# Power.net
KiCad netlist of a schematic drawn in Altium Designer
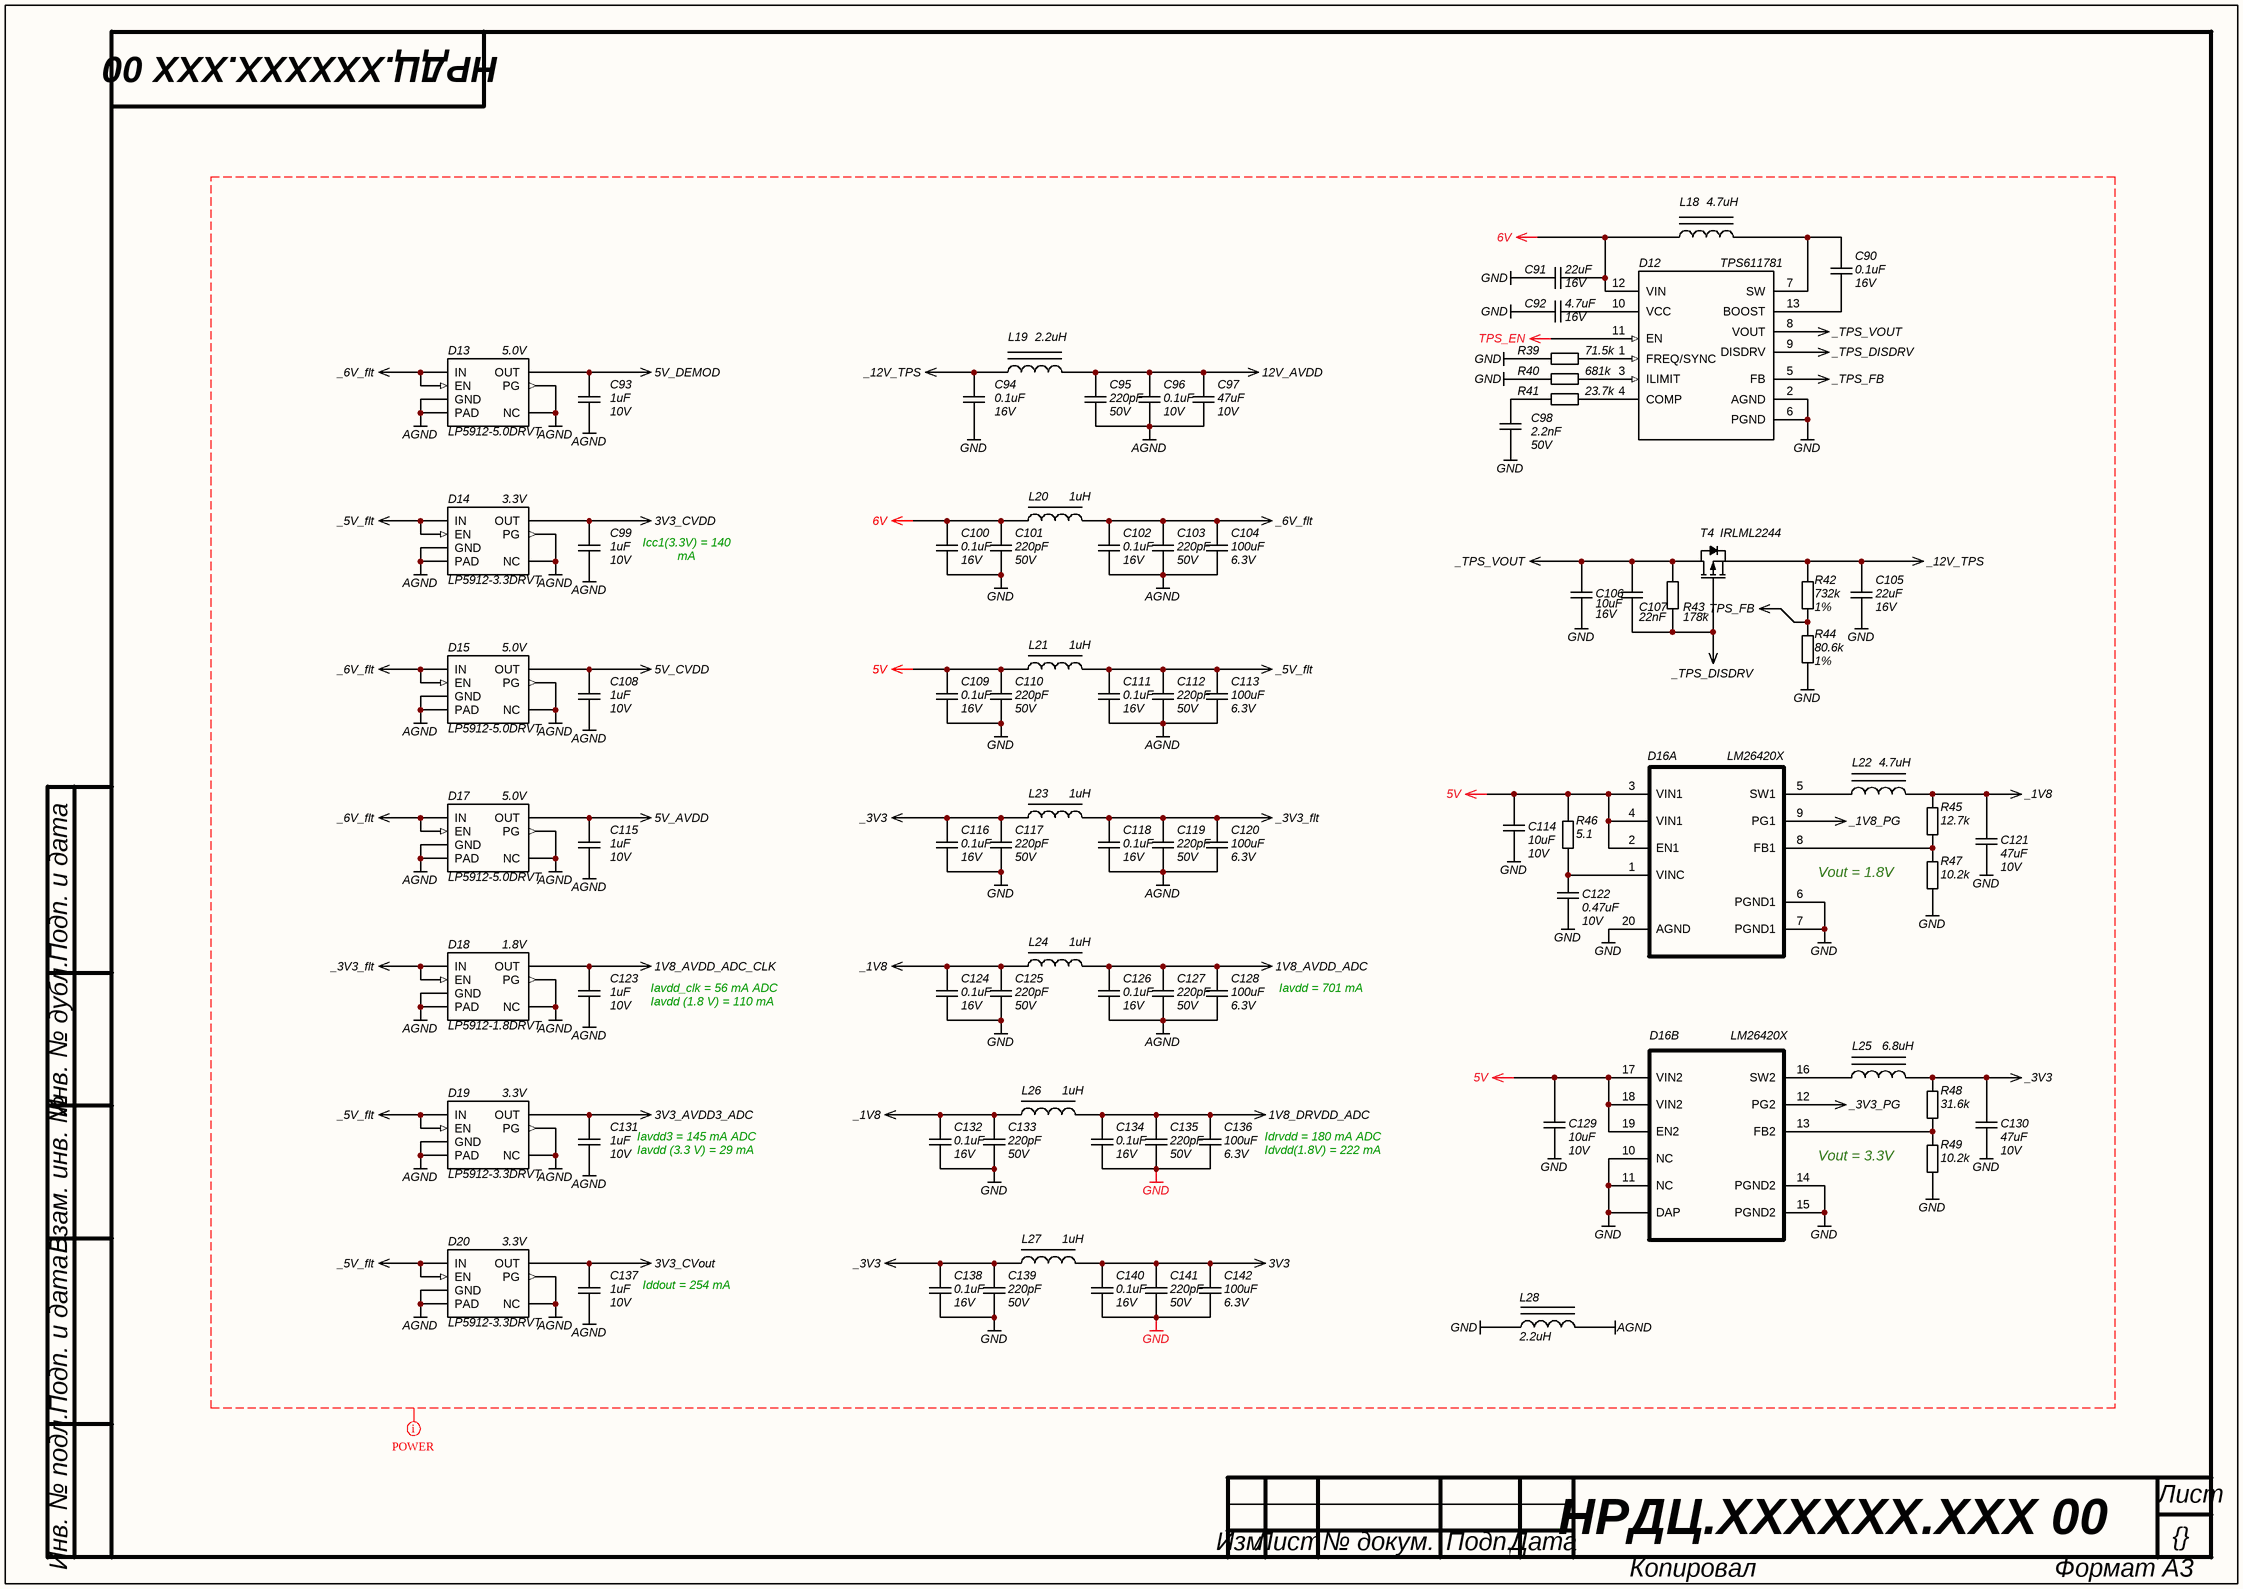
[diagram p0: Power.SchDoc]

(export (version "E")
  (design (tool "Eeschema 10.0.6"))
  (components
    (comp (ref "C90")
      (value "0.1uF")
      (footprint "C0402")
      (description "SMD Capacitor")
      (fields
        (field (name "MANUFACTURER") "Murata")
        (field (name "TOLERANCE") "±10%")
        (field (name "VOLTAGE") "16V")
      )
      (libsource (lib "Kintex_SDR") (part "CAP"))
    )
    (comp (ref "C91")
      (value "22uF")
      (footprint "C0805")
      (description "SMD Capacitor")
      (fields
        (field (name "MANUFACTURER") "Murata")
        (field (name "TOLERANCE") "±20%")
        (field (name "VOLTAGE") "16V")
      )
      (libsource (lib "Kintex_SDR") (part "CAP uF"))
    )
    (comp (ref "C92")
      (value "4.7uF")
      (footprint "C0603")
      (description "SMD Capacitor")
      (fields
        (field (name "MANUFACTURER") "Murata")
        (field (name "TOLERANCE") "10%")
        (field (name "VOLTAGE") "16V")
      )
      (libsource (lib "Kintex_SDR") (part "CAP"))
    )
    (comp (ref "C93")
      (value "1uF")
      (footprint "C0805")
      (description "SMD Capacitor")
      (fields
        (field (name "MANUFACTURER") "Murata")
        (field (name "TOLERANCE") "10%")
        (field (name "VOLTAGE") "10V")
      )
      (libsource (lib "Kintex_SDR") (part "CAP"))
    )
    (comp (ref "C94")
      (value "0.1uF")
      (footprint "C0402")
      (description "SMD Capacitor")
      (fields
        (field (name "MANUFACTURER") "Murata")
        (field (name "TOLERANCE") "±10%")
        (field (name "VOLTAGE") "16V")
      )
      (libsource (lib "Kintex_SDR") (part "CAP"))
    )
    (comp (ref "C95")
      (value "220pF")
      (footprint "C0603")
      (description "SMD Capacitor")
      (fields
        (field (name "MANUFACTURER") "Murata")
        (field (name "TOLERANCE") "10%")
        (field (name "VOLTAGE") "50V")
      )
      (libsource (lib "Kintex_SDR") (part "CAP"))
    )
    (comp (ref "C96")
      (value "0.1uF")
      (footprint "C0402")
      (description "SMD Capacitor")
      (fields
        (field (name "MANUFACTURER") "Murata")
        (field (name "TOLERANCE") "10%")
        (field (name "VOLTAGE") "10V")
      )
      (libsource (lib "Kintex_SDR") (part "CAP"))
    )
    (comp (ref "C97")
      (value "47uF")
      (footprint "C1210")
      (description "SMD Capacitor")
      (fields
        (field (name "MANUFACTURER") "Murata")
        (field (name "TOLERANCE") "10%")
        (field (name "VOLTAGE") "10V")
      )
      (libsource (lib "Kintex_SDR") (part "CAP uF"))
    )
    (comp (ref "C98")
      (value "2.2nF")
      (footprint "C0603")
      (description "SMD Capacitor")
      (fields
        (field (name "MANUFACTURER") "Murata")
        (field (name "TOLERANCE") "±5%")
        (field (name "VOLTAGE") "50V")
      )
      (libsource (lib "Kintex_SDR") (part "CAP"))
    )
    (comp (ref "C99")
      (value "1uF")
      (footprint "C0805")
      (description "SMD Capacitor")
      (fields
        (field (name "MANUFACTURER") "Murata")
        (field (name "TOLERANCE") "10%")
        (field (name "VOLTAGE") "10V")
      )
      (libsource (lib "Kintex_SDR") (part "CAP"))
    )
    (comp (ref "C100")
      (value "0.1uF")
      (footprint "C0603")
      (description "SMD Capacitor")
      (fields
        (field (name "MANUFACTURER") "Murata")
        (field (name "TOLERANCE") "10%")
        (field (name "VOLTAGE") "16V")
      )
      (libsource (lib "Kintex_SDR") (part "CAP"))
    )
    (comp (ref "C101")
      (value "220pF")
      (footprint "C0603")
      (description "SMD Capacitor")
      (fields
        (field (name "MANUFACTURER") "Murata")
        (field (name "TOLERANCE") "10%")
        (field (name "VOLTAGE") "50V")
      )
      (libsource (lib "Kintex_SDR") (part "CAP"))
    )
    (comp (ref "C102")
      (value "0.1uF")
      (footprint "C0603")
      (description "SMD Capacitor")
      (fields
        (field (name "MANUFACTURER") "Murata")
        (field (name "TOLERANCE") "10%")
        (field (name "VOLTAGE") "16V")
      )
      (libsource (lib "Kintex_SDR") (part "CAP"))
    )
    (comp (ref "C103")
      (value "220pF")
      (footprint "C0603")
      (description "SMD Capacitor")
      (fields
        (field (name "MANUFACTURER") "Murata")
        (field (name "TOLERANCE") "10%")
        (field (name "VOLTAGE") "50V")
      )
      (libsource (lib "Kintex_SDR") (part "CAP"))
    )
    (comp (ref "C104")
      (value "100uF")
      (footprint "C1210")
      (description "SMD Capacitor")
      (fields
        (field (name "MANUFACTURER") "Murata")
        (field (name "TOLERANCE") "20%")
        (field (name "VOLTAGE") "6.3V")
      )
      (libsource (lib "Kintex_SDR") (part "CAP uF"))
    )
    (comp (ref "C105")
      (value "22uF")
      (footprint "C0805")
      (description "SMD Capacitor")
      (fields
        (field (name "MANUFACTURER") "Murata")
        (field (name "TOLERANCE") "±20%")
        (field (name "VOLTAGE") "16V")
      )
      (libsource (lib "Kintex_SDR") (part "CAP uF"))
    )
    (comp (ref "C106")
      (value "10uF")
      (footprint "C0805")
      (description "SMD Capacitor")
      (fields
        (field (name "MANUFACTURER") "Murata")
        (field (name "TOLERANCE") "±10%")
        (field (name "VOLTAGE") "16V")
      )
      (libsource (lib "Kintex_SDR") (part "CAP uF"))
    )
    (comp (ref "C107")
      (value "22nF")
      (footprint "C0402")
      (description "SMD Capacitor")
      (fields (field (name "MANUFACTURER") "Murata") (field (name "TOLERANCE") "10%"))
      (libsource (lib "Kintex_SDR") (part "CAP"))
    )
    (comp (ref "C108")
      (value "1uF")
      (footprint "C0805")
      (description "SMD Capacitor")
      (fields
        (field (name "MANUFACTURER") "Murata")
        (field (name "TOLERANCE") "10%")
        (field (name "VOLTAGE") "10V")
      )
      (libsource (lib "Kintex_SDR") (part "CAP"))
    )
    (comp (ref "C109")
      (value "0.1uF")
      (footprint "C0603")
      (description "SMD Capacitor")
      (fields
        (field (name "MANUFACTURER") "Murata")
        (field (name "TOLERANCE") "10%")
        (field (name "VOLTAGE") "16V")
      )
      (libsource (lib "Kintex_SDR") (part "CAP"))
    )
    (comp (ref "C110")
      (value "220pF")
      (footprint "C0603")
      (description "SMD Capacitor")
      (fields
        (field (name "MANUFACTURER") "Murata")
        (field (name "TOLERANCE") "10%")
        (field (name "VOLTAGE") "50V")
      )
      (libsource (lib "Kintex_SDR") (part "CAP"))
    )
    (comp (ref "C111")
      (value "0.1uF")
      (footprint "C0603")
      (description "SMD Capacitor")
      (fields
        (field (name "MANUFACTURER") "Murata")
        (field (name "TOLERANCE") "10%")
        (field (name "VOLTAGE") "16V")
      )
      (libsource (lib "Kintex_SDR") (part "CAP"))
    )
    (comp (ref "C112")
      (value "220pF")
      (footprint "C0603")
      (description "SMD Capacitor")
      (fields
        (field (name "MANUFACTURER") "Murata")
        (field (name "TOLERANCE") "10%")
        (field (name "VOLTAGE") "50V")
      )
      (libsource (lib "Kintex_SDR") (part "CAP"))
    )
    (comp (ref "C113")
      (value "100uF")
      (footprint "C1210")
      (description "SMD Capacitor")
      (fields
        (field (name "MANUFACTURER") "Murata")
        (field (name "TOLERANCE") "20%")
        (field (name "VOLTAGE") "6.3V")
      )
      (libsource (lib "Kintex_SDR") (part "CAP uF"))
    )
    (comp (ref "C114")
      (value "10uF")
      (footprint "C0805")
      (description "SMD Capacitor")
      (fields
        (field (name "MANUFACTURER") "Murata")
        (field (name "TOLERANCE") "10%")
        (field (name "VOLTAGE") "10V")
      )
      (libsource (lib "Kintex_SDR") (part "CAP uF"))
    )
    (comp (ref "C115")
      (value "1uF")
      (footprint "C0805")
      (description "SMD Capacitor")
      (fields
        (field (name "MANUFACTURER") "Murata")
        (field (name "TOLERANCE") "10%")
        (field (name "VOLTAGE") "10V")
      )
      (libsource (lib "Kintex_SDR") (part "CAP"))
    )
    (comp (ref "C116")
      (value "0.1uF")
      (footprint "C0603")
      (description "SMD Capacitor")
      (fields
        (field (name "MANUFACTURER") "Murata")
        (field (name "TOLERANCE") "10%")
        (field (name "VOLTAGE") "16V")
      )
      (libsource (lib "Kintex_SDR") (part "CAP"))
    )
    (comp (ref "C117")
      (value "220pF")
      (footprint "C0603")
      (description "SMD Capacitor")
      (fields
        (field (name "MANUFACTURER") "Murata")
        (field (name "TOLERANCE") "10%")
        (field (name "VOLTAGE") "50V")
      )
      (libsource (lib "Kintex_SDR") (part "CAP"))
    )
    (comp (ref "C118")
      (value "0.1uF")
      (footprint "C0603")
      (description "SMD Capacitor")
      (fields
        (field (name "MANUFACTURER") "Murata")
        (field (name "TOLERANCE") "10%")
        (field (name "VOLTAGE") "16V")
      )
      (libsource (lib "Kintex_SDR") (part "CAP"))
    )
    (comp (ref "C119")
      (value "220pF")
      (footprint "C0603")
      (description "SMD Capacitor")
      (fields
        (field (name "MANUFACTURER") "Murata")
        (field (name "TOLERANCE") "10%")
        (field (name "VOLTAGE") "50V")
      )
      (libsource (lib "Kintex_SDR") (part "CAP"))
    )
    (comp (ref "C120")
      (value "100uF")
      (footprint "C1210")
      (description "SMD Capacitor")
      (fields
        (field (name "MANUFACTURER") "Murata")
        (field (name "TOLERANCE") "20%")
        (field (name "VOLTAGE") "6.3V")
      )
      (libsource (lib "Kintex_SDR") (part "CAP uF"))
    )
    (comp (ref "C121")
      (value "47uF")
      (footprint "C1210")
      (description "SMD Capacitor")
      (fields
        (field (name "MANUFACTURER") "Murata")
        (field (name "TOLERANCE") "10%")
        (field (name "VOLTAGE") "10V")
      )
      (libsource (lib "Kintex_SDR") (part "CAP uF"))
    )
    (comp (ref "C122")
      (value "0.47uF")
      (footprint "C0603")
      (description "SMD Capacitor")
      (fields
        (field (name "MANUFACTURER") "Murata")
        (field (name "TOLERANCE") "10%")
        (field (name "VOLTAGE") "10V")
      )
      (libsource (lib "Kintex_SDR") (part "CAP"))
    )
    (comp (ref "C123")
      (value "1uF")
      (footprint "C0805")
      (description "SMD Capacitor")
      (fields
        (field (name "MANUFACTURER") "Murata")
        (field (name "TOLERANCE") "10%")
        (field (name "VOLTAGE") "10V")
      )
      (libsource (lib "Kintex_SDR") (part "CAP"))
    )
    (comp (ref "C124")
      (value "0.1uF")
      (footprint "C0603")
      (description "SMD Capacitor")
      (fields
        (field (name "MANUFACTURER") "Murata")
        (field (name "TOLERANCE") "10%")
        (field (name "VOLTAGE") "16V")
      )
      (libsource (lib "Kintex_SDR") (part "CAP"))
    )
    (comp (ref "C125")
      (value "220pF")
      (footprint "C0603")
      (description "SMD Capacitor")
      (fields
        (field (name "MANUFACTURER") "Murata")
        (field (name "TOLERANCE") "10%")
        (field (name "VOLTAGE") "50V")
      )
      (libsource (lib "Kintex_SDR") (part "CAP"))
    )
    (comp (ref "C126")
      (value "0.1uF")
      (footprint "C0603")
      (description "SMD Capacitor")
      (fields
        (field (name "MANUFACTURER") "Murata")
        (field (name "TOLERANCE") "10%")
        (field (name "VOLTAGE") "16V")
      )
      (libsource (lib "Kintex_SDR") (part "CAP"))
    )
    (comp (ref "C127")
      (value "220pF")
      (footprint "C0603")
      (description "SMD Capacitor")
      (fields
        (field (name "MANUFACTURER") "Murata")
        (field (name "TOLERANCE") "10%")
        (field (name "VOLTAGE") "50V")
      )
      (libsource (lib "Kintex_SDR") (part "CAP"))
    )
    (comp (ref "C128")
      (value "100uF")
      (footprint "C1210")
      (description "SMD Capacitor")
      (fields
        (field (name "MANUFACTURER") "Murata")
        (field (name "TOLERANCE") "20%")
        (field (name "VOLTAGE") "6.3V")
      )
      (libsource (lib "Kintex_SDR") (part "CAP uF"))
    )
    (comp (ref "C129")
      (value "10uF")
      (footprint "C0805")
      (description "SMD Capacitor")
      (fields
        (field (name "MANUFACTURER") "Murata")
        (field (name "TOLERANCE") "10%")
        (field (name "VOLTAGE") "10V")
      )
      (libsource (lib "Kintex_SDR") (part "CAP uF"))
    )
    (comp (ref "C130")
      (value "47uF")
      (footprint "C1210")
      (description "SMD Capacitor")
      (fields
        (field (name "MANUFACTURER") "Murata")
        (field (name "TOLERANCE") "10%")
        (field (name "VOLTAGE") "10V")
      )
      (libsource (lib "Kintex_SDR") (part "CAP uF"))
    )
    (comp (ref "C131")
      (value "1uF")
      (footprint "C0805")
      (description "SMD Capacitor")
      (fields
        (field (name "MANUFACTURER") "Murata")
        (field (name "TOLERANCE") "10%")
        (field (name "VOLTAGE") "10V")
      )
      (libsource (lib "Kintex_SDR") (part "CAP"))
    )
    (comp (ref "C132")
      (value "0.1uF")
      (footprint "C0603")
      (description "SMD Capacitor")
      (fields
        (field (name "MANUFACTURER") "Murata")
        (field (name "TOLERANCE") "10%")
        (field (name "VOLTAGE") "16V")
      )
      (libsource (lib "Kintex_SDR") (part "CAP"))
    )
    (comp (ref "C133")
      (value "220pF")
      (footprint "C0603")
      (description "SMD Capacitor")
      (fields
        (field (name "MANUFACTURER") "Murata")
        (field (name "TOLERANCE") "10%")
        (field (name "VOLTAGE") "50V")
      )
      (libsource (lib "Kintex_SDR") (part "CAP"))
    )
    (comp (ref "C134")
      (value "0.1uF")
      (footprint "C0603")
      (description "SMD Capacitor")
      (fields
        (field (name "MANUFACTURER") "Murata")
        (field (name "TOLERANCE") "10%")
        (field (name "VOLTAGE") "16V")
      )
      (libsource (lib "Kintex_SDR") (part "CAP"))
    )
    (comp (ref "C135")
      (value "220pF")
      (footprint "C0603")
      (description "SMD Capacitor")
      (fields
        (field (name "MANUFACTURER") "Murata")
        (field (name "TOLERANCE") "10%")
        (field (name "VOLTAGE") "50V")
      )
      (libsource (lib "Kintex_SDR") (part "CAP"))
    )
    (comp (ref "C136")
      (value "100uF")
      (footprint "C1210")
      (description "SMD Capacitor")
      (fields
        (field (name "MANUFACTURER") "Murata")
        (field (name "TOLERANCE") "20%")
        (field (name "VOLTAGE") "6.3V")
      )
      (libsource (lib "Kintex_SDR") (part "CAP uF"))
    )
    (comp (ref "C137")
      (value "1uF")
      (footprint "C0805")
      (description "SMD Capacitor")
      (fields
        (field (name "MANUFACTURER") "Murata")
        (field (name "TOLERANCE") "10%")
        (field (name "VOLTAGE") "10V")
      )
      (libsource (lib "Kintex_SDR") (part "CAP"))
    )
    (comp (ref "C138")
      (value "0.1uF")
      (footprint "C0603")
      (description "SMD Capacitor")
      (fields
        (field (name "MANUFACTURER") "Murata")
        (field (name "TOLERANCE") "10%")
        (field (name "VOLTAGE") "16V")
      )
      (libsource (lib "Kintex_SDR") (part "CAP"))
    )
    (comp (ref "C139")
      (value "220pF")
      (footprint "C0603")
      (description "SMD Capacitor")
      (fields
        (field (name "MANUFACTURER") "Murata")
        (field (name "TOLERANCE") "10%")
        (field (name "VOLTAGE") "50V")
      )
      (libsource (lib "Kintex_SDR") (part "CAP"))
    )
    (comp (ref "C140")
      (value "0.1uF")
      (footprint "C0603")
      (description "SMD Capacitor")
      (fields
        (field (name "MANUFACTURER") "Murata")
        (field (name "TOLERANCE") "10%")
        (field (name "VOLTAGE") "16V")
      )
      (libsource (lib "Kintex_SDR") (part "CAP"))
    )
    (comp (ref "C141")
      (value "220pF")
      (footprint "C0603")
      (description "SMD Capacitor")
      (fields
        (field (name "MANUFACTURER") "Murata")
        (field (name "TOLERANCE") "10%")
        (field (name "VOLTAGE") "50V")
      )
      (libsource (lib "Kintex_SDR") (part "CAP"))
    )
    (comp (ref "C142")
      (value "100uF")
      (footprint "C1210")
      (description "SMD Capacitor")
      (fields
        (field (name "MANUFACTURER") "Murata")
        (field (name "TOLERANCE") "20%")
        (field (name "VOLTAGE") "6.3V")
      )
      (libsource (lib "Kintex_SDR") (part "CAP uF"))
    )
    (comp (ref "D12")
      (value "TPS611781")
      (footprint "DBLib:TPS611781x")
      (description "10-A Fully-Integrated Synchronous Boost with Load Disconnect Control")
      (fields (field (name "MANUFACTURER") "Texas Instruments") (field (name "VOLTAGE") "4.5 V to 20 V"))
      (libsource (lib "DBLib") (part "TPS611781"))
    )
    (comp (ref "D13")
      (value "LP5912")
      (footprint "DBLib:WSON-6")
      (description "LP5912 500-mA Low-Noise, Low-IQ LDO")
      (fields
        (field (name "MANUFACTURER") "Texas Instruments")
        (field (name "NAME") "LP5912-5.0DRVT")
        (field (name "VOLTAGE") "5.0V")
      )
      (libsource (lib "DBLib") (part "LP5912"))
    )
    (comp (ref "D14")
      (value "LP5912")
      (footprint "DBLib:WSON-6")
      (description "LP5912 500-mA Low-Noise, Low-IQ LDO")
      (fields
        (field (name "MANUFACTURER") "Texas Instruments")
        (field (name "NAME") "LP5912-3.3DRVT")
        (field (name "VOLTAGE") "3.3V")
      )
      (libsource (lib "DBLib") (part "LP5912"))
    )
    (comp (ref "D15")
      (value "LP5912")
      (footprint "DBLib:WSON-6")
      (description "LP5912 500-mA Low-Noise, Low-IQ LDO")
      (fields
        (field (name "MANUFACTURER") "Texas Instruments")
        (field (name "NAME") "LP5912-5.0DRVT")
        (field (name "VOLTAGE") "5.0V")
      )
      (libsource (lib "DBLib") (part "LP5912"))
    )
    (comp (ref "D16")
      (value "LM26420X")
      (footprint "HTSSOP-20")
      (description "Synchronous  DC-DC Converter")
      (libsource (lib "Kintex_SDR") (part "LM26420X"))
    )
    (comp (ref "D17")
      (value "LP5912")
      (footprint "DBLib:WSON-6")
      (description "LP5912 500-mA Low-Noise, Low-IQ LDO")
      (fields
        (field (name "MANUFACTURER") "Texas Instruments")
        (field (name "NAME") "LP5912-5.0DRVT")
        (field (name "VOLTAGE") "5.0V")
      )
      (libsource (lib "DBLib") (part "LP5912"))
    )
    (comp (ref "D18")
      (value "LP5912")
      (footprint "DBLib:WSON-6")
      (description "LP5912 500-mA Low-Noise, Low-IQ LDO")
      (fields
        (field (name "MANUFACTURER") "Texas Instruments")
        (field (name "NAME") "LP5912-1.8DRVT")
        (field (name "VOLTAGE") "1.8V")
      )
      (libsource (lib "DBLib") (part "LP5912"))
    )
    (comp (ref "D19")
      (value "LP5912")
      (footprint "DBLib:WSON-6")
      (description "LP5912 500-mA Low-Noise, Low-IQ LDO")
      (fields
        (field (name "MANUFACTURER") "Texas Instruments")
        (field (name "NAME") "LP5912-3.3DRVT")
        (field (name "VOLTAGE") "3.3V")
      )
      (libsource (lib "DBLib") (part "LP5912"))
    )
    (comp (ref "D20")
      (value "LP5912")
      (footprint "DBLib:WSON-6")
      (description "LP5912 500-mA Low-Noise, Low-IQ LDO")
      (fields
        (field (name "MANUFACTURER") "Texas Instruments")
        (field (name "NAME") "LP5912-3.3DRVT")
        (field (name "VOLTAGE") "3.3V")
      )
      (libsource (lib "DBLib") (part "LP5912"))
    )
    (comp (ref "L18")
      (value "4.7uH")
      (footprint "XAL4030")
      (description "Magnetic-Core Inductor")
      (fields (field (name "MANUFACTURER") "Coilcraft") (field (name "TOLERANCE") "±20%"))
      (libsource (lib "Kintex_SDR") (part "Inductor PWR"))
    )
    (comp (ref "L19")
      (value "2.2uH")
      (footprint "XAL4030")
      (description "Magnetic-Core Inductor")
      (fields (field (name "MANUFACTURER") "Coilcraft") (field (name "TOLERANCE") "±30%"))
      (libsource (lib "Kintex_SDR") (part "Inductor PWR"))
    )
    (comp (ref "L20")
      (value "1uH")
      (footprint "L1210_Murata LQH")
      (description "Inductor Power Lines")
      (fields (field (name "MANUFACTURER") "Murata") (field (name "TOLERANCE") "5%"))
      (libsource (lib "Kintex_SDR") (part "Inductor LF"))
    )
    (comp (ref "L21")
      (value "1uH")
      (footprint "L1210_Murata LQH")
      (description "Inductor Power Lines")
      (fields (field (name "MANUFACTURER") "Murata") (field (name "TOLERANCE") "5%"))
      (libsource (lib "Kintex_SDR") (part "Inductor LF"))
    )
    (comp (ref "L22")
      (value "4.7uH")
      (footprint "XAL4030")
      (description "Magnetic-Core Inductor")
      (fields (field (name "MANUFACTURER") "Coilcraft") (field (name "TOLERANCE") "±20%"))
      (libsource (lib "Kintex_SDR") (part "Inductor PWR"))
    )
    (comp (ref "L23")
      (value "1uH")
      (footprint "L1210_Murata LQH")
      (description "Inductor Power Lines")
      (fields (field (name "MANUFACTURER") "Murata") (field (name "TOLERANCE") "5%"))
      (libsource (lib "Kintex_SDR") (part "Inductor LF"))
    )
    (comp (ref "L24")
      (value "1uH")
      (footprint "L1210_Murata LQH")
      (description "Inductor Power Lines")
      (fields (field (name "MANUFACTURER") "Murata") (field (name "TOLERANCE") "5%"))
      (libsource (lib "Kintex_SDR") (part "Inductor LF"))
    )
    (comp (ref "L25")
      (value "6.8uH")
      (footprint "XAL4030")
      (description "Magnetic-Core Inductor")
      (fields (field (name "MANUFACTURER") "Coilcraft") (field (name "TOLERANCE") "±20%"))
      (libsource (lib "Kintex_SDR") (part "Inductor PWR"))
    )
    (comp (ref "L26")
      (value "1uH")
      (footprint "L1210_Murata LQH")
      (description "Inductor Power Lines")
      (fields (field (name "MANUFACTURER") "Murata") (field (name "TOLERANCE") "5%"))
      (libsource (lib "Kintex_SDR") (part "Inductor LF"))
    )
    (comp (ref "L27")
      (value "1uH")
      (footprint "L1210_Murata LQH")
      (description "Inductor Power Lines")
      (fields (field (name "MANUFACTURER") "Murata") (field (name "TOLERANCE") "5%"))
      (libsource (lib "Kintex_SDR") (part "Inductor LF"))
    )
    (comp (ref "L28")
      (value "2.2uH")
      (footprint "XAL4030")
      (description "Magnetic-Core Inductor")
      (fields (field (name "MANUFACTURER") "Coilcraft") (field (name "TOLERANCE") "±30%"))
      (libsource (lib "Kintex_SDR") (part "Inductor PWR"))
    )
    (comp (ref "R39")
      (value "71.5k")
      (footprint "R0402")
      (description "SMD Resistor")
      (fields (field (name "POWER") "0.063 Wt") (field (name "TOLERANCE") "1%"))
      (libsource (lib "Kintex_SDR") (part "RES"))
    )
    (comp (ref "R40")
      (value "681k")
      (footprint "R0402")
      (description "SMD Resistor")
      (fields (field (name "POWER") "0.063 Wt") (field (name "TOLERANCE") "1%"))
      (libsource (lib "Kintex_SDR") (part "RES"))
    )
    (comp (ref "R41")
      (value "23.7k")
      (footprint "R0603")
      (description "SMD Resistor")
      (fields (field (name "POWER") "0.1 Wt") (field (name "TOLERANCE") "1%"))
      (libsource (lib "Kintex_SDR") (part "RES"))
    )
    (comp (ref "R42")
      (value "732k")
      (footprint "R0402")
      (description "SMD Resistor")
      (fields
        (field (name "POWER") "0.063 Wt")
        (field (name "TOLERANCE") "1%")
        (field (name "MANUFACTURER") "Panasonic Electronic Components")
      )
      (libsource (lib "") (part "RES_1"))
    )
    (comp (ref "R43")
      (value "178k")
      (footprint "R0402")
      (description "SMD Resistor")
      (fields (field (name "POWER") "0.063 Wt") (field (name "TOLERANCE") "1%"))
      (libsource (lib "") (part "RES_1"))
    )
    (comp (ref "R44")
      (value "80.6k")
      (footprint "R0402")
      (description "SMD Resistor")
      (fields
        (field (name "POWER") "0.063 Wt")
        (field (name "TOLERANCE") "1%")
        (field (name "MANUFACTURER") "Panasonic Electronic Components")
      )
      (libsource (lib "") (part "RES_1"))
    )
    (comp (ref "R45")
      (value "12.7k")
      (footprint "R0402")
      (description "SMD Resistor")
      (fields (field (name "POWER") "0.062 Wt") (field (name "TOLERANCE") "1%"))
      (libsource (lib "") (part "RES_1"))
    )
    (comp (ref "R46")
      (value "5.1")
      (footprint "R0402")
      (description "SMD Resistor")
      (fields (field (name "POWER") "0.062 Wt") (field (name "TOLERANCE") "5%"))
      (libsource (lib "") (part "RES_1"))
    )
    (comp (ref "R47")
      (value "10.2k")
      (footprint "R0402")
      (description "SMD Resistor")
      (fields (field (name "POWER") "0.062 Wt") (field (name "TOLERANCE") "1%"))
      (libsource (lib "") (part "RES_1"))
    )
    (comp (ref "R48")
      (value "31.6k")
      (footprint "R0402")
      (description "SMD Resistor")
      (fields (field (name "POWER") "0.062 Wt") (field (name "TOLERANCE") "1%"))
      (libsource (lib "") (part "RES_1"))
    )
    (comp (ref "R49")
      (value "10.2k")
      (footprint "R0402")
      (description "SMD Resistor")
      (fields (field (name "POWER") "0.062 Wt") (field (name "TOLERANCE") "1%"))
      (libsource (lib "") (part "RES_1"))
    )
    (comp (ref "T4")
      (value "IRLML2244")
      (footprint "DBLib:SOT-23")
      (description "P-Channel MOSFET")
      (fields (field (name "VOLTAGE") "-20V"))
      (libsource (lib "DBLib") (part "IRLML2244"))
    )
  )
  (nets
    (net (code "1") (name "1V8_AVDD_ADC") (class "Default")
      (node (ref "C126") (pin "2") (pinfunction "2_2") (pintype "passive"))
      (node (ref "C127") (pin "2") (pinfunction "2_2") (pintype "passive"))
      (node (ref "C128") (pin "2") (pinfunction "2_2") (pintype "passive"))
      (node (ref "L24") (pin "2") (pinfunction "2_2") (pintype "passive"))
    )
    (net (code "2") (name "1V8_AVDD_ADC_CLK") (class "Default")
      (node (ref "C123") (pin "1") (pinfunction "1_1") (pintype "passive"))
      (node (ref "D18") (pin "1") (pinfunction "OUT_1") (pintype "passive"))
    )
    (net (code "3") (name "1V8_DRVDD_ADC") (class "Default")
      (node (ref "C134") (pin "2") (pinfunction "2_2") (pintype "passive"))
      (node (ref "C135") (pin "2") (pinfunction "2_2") (pintype "passive"))
      (node (ref "C136") (pin "2") (pinfunction "2_2") (pintype "passive"))
      (node (ref "L26") (pin "2") (pinfunction "2_2") (pintype "passive"))
    )
    (net (code "4") (name "3V3") (class "Default")
      (node (ref "C140") (pin "2") (pinfunction "2_2") (pintype "passive"))
      (node (ref "C141") (pin "2") (pinfunction "2_2") (pintype "passive"))
      (node (ref "C142") (pin "2") (pinfunction "2_2") (pintype "passive"))
      (node (ref "L27") (pin "2") (pinfunction "2_2") (pintype "passive"))
    )
    (net (code "5") (name "3V3_AVDD3_ADC") (class "Default")
      (node (ref "C131") (pin "1") (pinfunction "1_1") (pintype "passive"))
      (node (ref "D19") (pin "1") (pinfunction "OUT_1") (pintype "passive"))
    )
    (net (code "6") (name "3V3_CVDD") (class "Default")
      (node (ref "C99") (pin "1") (pinfunction "1_1") (pintype "passive"))
      (node (ref "D14") (pin "1") (pinfunction "OUT_1") (pintype "passive"))
    )
    (net (code "7") (name "3V3_CVout") (class "Default")
      (node (ref "C137") (pin "1") (pinfunction "1_1") (pintype "passive"))
      (node (ref "D20") (pin "1") (pinfunction "OUT_1") (pintype "passive"))
    )
    (net (code "8") (name "5V") (class "Default")
      (node (ref "C109") (pin "2") (pinfunction "2_2") (pintype "passive"))
      (node (ref "C110") (pin "2") (pinfunction "2_2") (pintype "passive"))
      (node (ref "C114") (pin "2") (pinfunction "2_2") (pintype "passive"))
      (node (ref "C129") (pin "2") (pinfunction "2_2") (pintype "passive"))
      (node (ref "D16") (pin "17") (pinfunction "VIN2_17") (pintype "passive"))
      (node (ref "D16") (pin "18") (pinfunction "VIN2_18") (pintype "passive"))
      (node (ref "D16") (pin "19") (pinfunction "EN2_19") (pintype "passive"))
      (node (ref "D16") (pin "2") (pinfunction "EN1_2") (pintype "passive"))
      (node (ref "D16") (pin "3") (pinfunction "VIN1_3") (pintype "passive"))
      (node (ref "D16") (pin "4") (pinfunction "VIN1_4") (pintype "passive"))
      (node (ref "L21") (pin "1") (pinfunction "1_1") (pintype "passive"))
      (node (ref "R46") (pin "2") (pinfunction "2_2") (pintype "passive"))
    )
    (net (code "9") (name "5V_AVDD") (class "Default")
      (node (ref "C115") (pin "1") (pinfunction "1_1") (pintype "passive"))
      (node (ref "D17") (pin "1") (pinfunction "OUT_1") (pintype "passive"))
    )
    (net (code "10") (name "5V_CVDD") (class "Default")
      (node (ref "C108") (pin "1") (pinfunction "1_1") (pintype "passive"))
      (node (ref "D15") (pin "1") (pinfunction "OUT_1") (pintype "passive"))
    )
    (net (code "11") (name "5V_DEMOD") (class "Default")
      (node (ref "C93") (pin "1") (pinfunction "1_1") (pintype "passive"))
      (node (ref "D13") (pin "1") (pinfunction "OUT_1") (pintype "passive"))
    )
    (net (code "12") (name "6V") (class "Default")
      (node (ref "C100") (pin "2") (pinfunction "2_2") (pintype "passive"))
      (node (ref "C101") (pin "2") (pinfunction "2_2") (pintype "passive"))
      (node (ref "C91") (pin "1") (pinfunction "1_1") (pintype "passive"))
      (node (ref "D12") (pin "12") (pinfunction "VIN_12") (pintype "passive"))
      (node (ref "L18") (pin "1") (pinfunction "1_1") (pintype "passive"))
      (node (ref "L20") (pin "1") (pinfunction "1_1") (pintype "passive"))
    )
    (net (code "13") (name "12V_AVDD") (class "Default")
      (node (ref "C95") (pin "2") (pinfunction "2_2") (pintype "passive"))
      (node (ref "C96") (pin "2") (pinfunction "2_2") (pintype "passive"))
      (node (ref "C97") (pin "2") (pinfunction "2_2") (pintype "passive"))
      (node (ref "L19") (pin "2") (pinfunction "2_2") (pintype "passive"))
    )
    (net (code "14") (name "AGND") (class "Default")
      (node (ref "C102") (pin "1") (pinfunction "1_1") (pintype "passive"))
      (node (ref "C103") (pin "1") (pinfunction "1_1") (pintype "passive"))
      (node (ref "C104") (pin "1") (pinfunction "1_1") (pintype "passive"))
      (node (ref "C108") (pin "2") (pinfunction "2_2") (pintype "passive"))
      (node (ref "C111") (pin "1") (pinfunction "1_1") (pintype "passive"))
      (node (ref "C112") (pin "1") (pinfunction "1_1") (pintype "passive"))
      (node (ref "C113") (pin "1") (pinfunction "1_1") (pintype "passive"))
      (node (ref "C115") (pin "2") (pinfunction "2_2") (pintype "passive"))
      (node (ref "C118") (pin "1") (pinfunction "1_1") (pintype "passive"))
      (node (ref "C119") (pin "1") (pinfunction "1_1") (pintype "passive"))
      (node (ref "C120") (pin "1") (pinfunction "1_1") (pintype "passive"))
      (node (ref "C123") (pin "2") (pinfunction "2_2") (pintype "passive"))
      (node (ref "C126") (pin "1") (pinfunction "1_1") (pintype "passive"))
      (node (ref "C127") (pin "1") (pinfunction "1_1") (pintype "passive"))
      (node (ref "C128") (pin "1") (pinfunction "1_1") (pintype "passive"))
      (node (ref "C131") (pin "2") (pinfunction "2_2") (pintype "passive"))
      (node (ref "C137") (pin "2") (pinfunction "2_2") (pintype "passive"))
      (node (ref "C93") (pin "2") (pinfunction "2_2") (pintype "passive"))
      (node (ref "C95") (pin "1") (pinfunction "1_1") (pintype "passive"))
      (node (ref "C96") (pin "1") (pinfunction "1_1") (pintype "passive"))
      (node (ref "C97") (pin "1") (pinfunction "1_1") (pintype "passive"))
      (node (ref "C99") (pin "2") (pinfunction "2_2") (pintype "passive"))
      (node (ref "D13") (pin "0") (pinfunction "PAD_0") (pintype "passive"))
      (node (ref "D13") (pin "2") (pinfunction "NC_2") (pintype "passive"))
      (node (ref "D13") (pin "3") (pinfunction "PG_3") (pintype "output"))
      (node (ref "D13") (pin "5") (pinfunction "GND_5") (pintype "passive"))
      (node (ref "D14") (pin "0") (pinfunction "PAD_0") (pintype "passive"))
      (node (ref "D14") (pin "2") (pinfunction "NC_2") (pintype "passive"))
      (node (ref "D14") (pin "3") (pinfunction "PG_3") (pintype "output"))
      (node (ref "D14") (pin "5") (pinfunction "GND_5") (pintype "passive"))
      (node (ref "D15") (pin "0") (pinfunction "PAD_0") (pintype "passive"))
      (node (ref "D15") (pin "2") (pinfunction "NC_2") (pintype "passive"))
      (node (ref "D15") (pin "3") (pinfunction "PG_3") (pintype "output"))
      (node (ref "D15") (pin "5") (pinfunction "GND_5") (pintype "passive"))
      (node (ref "D17") (pin "0") (pinfunction "PAD_0") (pintype "passive"))
      (node (ref "D17") (pin "2") (pinfunction "NC_2") (pintype "passive"))
      (node (ref "D17") (pin "3") (pinfunction "PG_3") (pintype "output"))
      (node (ref "D17") (pin "5") (pinfunction "GND_5") (pintype "passive"))
      (node (ref "D18") (pin "0") (pinfunction "PAD_0") (pintype "passive"))
      (node (ref "D18") (pin "2") (pinfunction "NC_2") (pintype "passive"))
      (node (ref "D18") (pin "3") (pinfunction "PG_3") (pintype "output"))
      (node (ref "D18") (pin "5") (pinfunction "GND_5") (pintype "passive"))
      (node (ref "D19") (pin "0") (pinfunction "PAD_0") (pintype "passive"))
      (node (ref "D19") (pin "2") (pinfunction "NC_2") (pintype "passive"))
      (node (ref "D19") (pin "3") (pinfunction "PG_3") (pintype "output"))
      (node (ref "D19") (pin "5") (pinfunction "GND_5") (pintype "passive"))
      (node (ref "D20") (pin "0") (pinfunction "PAD_0") (pintype "passive"))
      (node (ref "D20") (pin "2") (pinfunction "NC_2") (pintype "passive"))
      (node (ref "D20") (pin "3") (pinfunction "PG_3") (pintype "output"))
      (node (ref "D20") (pin "5") (pinfunction "GND_5") (pintype "passive"))
      (node (ref "L28") (pin "2") (pinfunction "2_2") (pintype "passive"))
    )
    (net (code "15") (name "GND") (class "Default")
      (node (ref "C100") (pin "1") (pinfunction "1_1") (pintype "passive"))
      (node (ref "C101") (pin "1") (pinfunction "1_1") (pintype "passive"))
      (node (ref "C105") (pin "1") (pinfunction "1_1") (pintype "passive"))
      (node (ref "C106") (pin "1") (pinfunction "1_1") (pintype "passive"))
      (node (ref "C109") (pin "1") (pinfunction "1_1") (pintype "passive"))
      (node (ref "C110") (pin "1") (pinfunction "1_1") (pintype "passive"))
      (node (ref "C114") (pin "1") (pinfunction "1_1") (pintype "passive"))
      (node (ref "C116") (pin "1") (pinfunction "1_1") (pintype "passive"))
      (node (ref "C117") (pin "1") (pinfunction "1_1") (pintype "passive"))
      (node (ref "C121") (pin "1") (pinfunction "1_1") (pintype "passive"))
      (node (ref "C122") (pin "1") (pinfunction "1_1") (pintype "passive"))
      (node (ref "C124") (pin "1") (pinfunction "1_1") (pintype "passive"))
      (node (ref "C125") (pin "1") (pinfunction "1_1") (pintype "passive"))
      (node (ref "C129") (pin "1") (pinfunction "1_1") (pintype "passive"))
      (node (ref "C130") (pin "1") (pinfunction "1_1") (pintype "passive"))
      (node (ref "C132") (pin "1") (pinfunction "1_1") (pintype "passive"))
      (node (ref "C133") (pin "1") (pinfunction "1_1") (pintype "passive"))
      (node (ref "C134") (pin "1") (pinfunction "1_1") (pintype "passive"))
      (node (ref "C135") (pin "1") (pinfunction "1_1") (pintype "passive"))
      (node (ref "C136") (pin "1") (pinfunction "1_1") (pintype "passive"))
      (node (ref "C138") (pin "1") (pinfunction "1_1") (pintype "passive"))
      (node (ref "C139") (pin "1") (pinfunction "1_1") (pintype "passive"))
      (node (ref "C140") (pin "1") (pinfunction "1_1") (pintype "passive"))
      (node (ref "C141") (pin "1") (pinfunction "1_1") (pintype "passive"))
      (node (ref "C142") (pin "1") (pinfunction "1_1") (pintype "passive"))
      (node (ref "C91") (pin "2") (pinfunction "2_2") (pintype "passive"))
      (node (ref "C92") (pin "2") (pinfunction "2_2") (pintype "passive"))
      (node (ref "C94") (pin "1") (pinfunction "1_1") (pintype "passive"))
      (node (ref "C98") (pin "1") (pinfunction "1_1") (pintype "passive"))
      (node (ref "D12") (pin "2") (pinfunction "AGND_2") (pintype "passive"))
      (node (ref "D12") (pin "6") (pinfunction "PGND_6") (pintype "passive"))
      (node (ref "D16") (pin "10") (pinfunction "NC_10") (pintype "passive"))
      (node (ref "D16") (pin "11") (pinfunction "NC_11") (pintype "passive"))
      (node (ref "D16") (pin "14") (pinfunction "PGND2_14") (pintype "passive"))
      (node (ref "D16") (pin "15") (pinfunction "PGND2_15") (pintype "passive"))
      (node (ref "D16") (pin "20") (pinfunction "AGND_20") (pintype "passive"))
      (node (ref "D16") (pin "21") (pinfunction "DAP_21") (pintype "passive"))
      (node (ref "D16") (pin "6") (pinfunction "PGND1_6") (pintype "passive"))
      (node (ref "D16") (pin "7") (pinfunction "PGND1_7") (pintype "passive"))
      (node (ref "L28") (pin "1") (pinfunction "1_1") (pintype "passive"))
      (node (ref "R39") (pin "1") (pinfunction "1_1") (pintype "passive"))
      (node (ref "R40") (pin "1") (pinfunction "1_1") (pintype "passive"))
      (node (ref "R44") (pin "1") (pinfunction "1_1") (pintype "passive"))
      (node (ref "R47") (pin "1") (pinfunction "1_1") (pintype "passive"))
      (node (ref "R49") (pin "1") (pinfunction "1_1") (pintype "passive"))
    )
    (net (code "16") (name "Net-(C98-Pad2)") (class "Default")
      (node (ref "C98") (pin "2") (pinfunction "2_2") (pintype "passive"))
      (node (ref "R41") (pin "1") (pinfunction "1_1") (pintype "passive"))
    )
    (net (code "17") (name "Net-(D12-BOOST)") (class "Default")
      (node (ref "C90") (pin "1") (pinfunction "1_1") (pintype "passive"))
      (node (ref "D12") (pin "13") (pinfunction "BOOST_13") (pintype "passive"))
    )
    (net (code "18") (name "Net-(D12-COMP)") (class "Default")
      (node (ref "D12") (pin "4") (pinfunction "COMP_4") (pintype "passive"))
      (node (ref "R41") (pin "2") (pinfunction "2_2") (pintype "passive"))
    )
    (net (code "19") (name "Net-(D12-FREQ{slash}SYNC)") (class "Default")
      (node (ref "D12") (pin "1") (pinfunction "FREQ/SYNC_1") (pintype "input"))
      (node (ref "R39") (pin "2") (pinfunction "2_2") (pintype "passive"))
    )
    (net (code "20") (name "Net-(D12-ILIMIT)") (class "Default")
      (node (ref "D12") (pin "3") (pinfunction "ILIMIT_3") (pintype "input"))
      (node (ref "R40") (pin "2") (pinfunction "2_2") (pintype "passive"))
    )
    (net (code "21") (name "Net-(D12-SW)") (class "Default")
      (node (ref "C90") (pin "2") (pinfunction "2_2") (pintype "passive"))
      (node (ref "D12") (pin "7") (pinfunction "SW_7") (pintype "passive"))
      (node (ref "L18") (pin "2") (pinfunction "2_2") (pintype "passive"))
    )
    (net (code "22") (name "Net-(D12-VCC)") (class "Default")
      (node (ref "C92") (pin "1") (pinfunction "1_1") (pintype "passive"))
      (node (ref "D12") (pin "10") (pinfunction "VCC_10") (pintype "passive"))
    )
    (net (code "23") (name "Net-(D16A-FB1)") (class "Default")
      (node (ref "D16") (pin "8") (pinfunction "FB1_8") (pintype "passive"))
      (node (ref "R45") (pin "1") (pinfunction "1_1") (pintype "passive"))
      (node (ref "R47") (pin "2") (pinfunction "2_2") (pintype "passive"))
    )
    (net (code "24") (name "Net-(D16A-SW1)") (class "Default")
      (node (ref "D16") (pin "5") (pinfunction "SW1_5") (pintype "passive"))
      (node (ref "L22") (pin "1") (pinfunction "1_1") (pintype "passive"))
    )
    (net (code "25") (name "Net-(D16A-VINC)") (class "Default")
      (node (ref "C122") (pin "2") (pinfunction "2_2") (pintype "passive"))
      (node (ref "D16") (pin "1") (pinfunction "VINC_1") (pintype "passive"))
      (node (ref "R46") (pin "1") (pinfunction "1_1") (pintype "passive"))
    )
    (net (code "26") (name "Net-(D16B-FB2)") (class "Default")
      (node (ref "D16") (pin "13") (pinfunction "FB2_13") (pintype "passive"))
      (node (ref "R48") (pin "1") (pinfunction "1_1") (pintype "passive"))
      (node (ref "R49") (pin "2") (pinfunction "2_2") (pintype "passive"))
    )
    (net (code "27") (name "Net-(D16B-SW2)") (class "Default")
      (node (ref "D16") (pin "16") (pinfunction "SW2_16") (pintype "passive"))
      (node (ref "L25") (pin "1") (pinfunction "1_1") (pintype "passive"))
    )
    (net (code "28") (name "TPS_EN") (class "Default")
      (node (ref "D12") (pin "11") (pinfunction "EN_11") (pintype "input"))
    )
    (net (code "29") (name "_1V8") (class "Default")
      (node (ref "C121") (pin "2") (pinfunction "2_2") (pintype "passive"))
      (node (ref "C124") (pin "2") (pinfunction "2_2") (pintype "passive"))
      (node (ref "C125") (pin "2") (pinfunction "2_2") (pintype "passive"))
      (node (ref "C132") (pin "2") (pinfunction "2_2") (pintype "passive"))
      (node (ref "C133") (pin "2") (pinfunction "2_2") (pintype "passive"))
      (node (ref "L22") (pin "2") (pinfunction "2_2") (pintype "passive"))
      (node (ref "L24") (pin "1") (pinfunction "1_1") (pintype "passive"))
      (node (ref "L26") (pin "1") (pinfunction "1_1") (pintype "passive"))
      (node (ref "R45") (pin "2") (pinfunction "2_2") (pintype "passive"))
    )
    (net (code "30") (name "_1V8_PG") (class "Default")
      (node (ref "D16") (pin "9") (pinfunction "PG1_9") (pintype "passive"))
    )
    (net (code "31") (name "_3V3") (class "Default")
      (node (ref "C116") (pin "2") (pinfunction "2_2") (pintype "passive"))
      (node (ref "C117") (pin "2") (pinfunction "2_2") (pintype "passive"))
      (node (ref "C130") (pin "2") (pinfunction "2_2") (pintype "passive"))
      (node (ref "C138") (pin "2") (pinfunction "2_2") (pintype "passive"))
      (node (ref "C139") (pin "2") (pinfunction "2_2") (pintype "passive"))
      (node (ref "L23") (pin "1") (pinfunction "1_1") (pintype "passive"))
      (node (ref "L25") (pin "2") (pinfunction "2_2") (pintype "passive"))
      (node (ref "L27") (pin "1") (pinfunction "1_1") (pintype "passive"))
      (node (ref "R48") (pin "2") (pinfunction "2_2") (pintype "passive"))
    )
    (net (code "32") (name "_3V3_PG") (class "Default")
      (node (ref "D16") (pin "12") (pinfunction "PG2_12") (pintype "passive"))
    )
    (net (code "33") (name "_3V3_flt") (class "Default")
      (node (ref "C118") (pin "2") (pinfunction "2_2") (pintype "passive"))
      (node (ref "C119") (pin "2") (pinfunction "2_2") (pintype "passive"))
      (node (ref "C120") (pin "2") (pinfunction "2_2") (pintype "passive"))
      (node (ref "D18") (pin "4") (pinfunction "EN_4") (pintype "input"))
      (node (ref "D18") (pin "6") (pinfunction "IN_6") (pintype "passive"))
      (node (ref "L23") (pin "2") (pinfunction "2_2") (pintype "passive"))
    )
    (net (code "34") (name "_5V_flt") (class "Default")
      (node (ref "C111") (pin "2") (pinfunction "2_2") (pintype "passive"))
      (node (ref "C112") (pin "2") (pinfunction "2_2") (pintype "passive"))
      (node (ref "C113") (pin "2") (pinfunction "2_2") (pintype "passive"))
      (node (ref "D14") (pin "4") (pinfunction "EN_4") (pintype "input"))
      (node (ref "D14") (pin "6") (pinfunction "IN_6") (pintype "passive"))
      (node (ref "D19") (pin "4") (pinfunction "EN_4") (pintype "input"))
      (node (ref "D19") (pin "6") (pinfunction "IN_6") (pintype "passive"))
      (node (ref "D20") (pin "4") (pinfunction "EN_4") (pintype "input"))
      (node (ref "D20") (pin "6") (pinfunction "IN_6") (pintype "passive"))
      (node (ref "L21") (pin "2") (pinfunction "2_2") (pintype "passive"))
    )
    (net (code "35") (name "_6V_flt") (class "Default")
      (node (ref "C102") (pin "2") (pinfunction "2_2") (pintype "passive"))
      (node (ref "C103") (pin "2") (pinfunction "2_2") (pintype "passive"))
      (node (ref "C104") (pin "2") (pinfunction "2_2") (pintype "passive"))
      (node (ref "D13") (pin "4") (pinfunction "EN_4") (pintype "input"))
      (node (ref "D13") (pin "6") (pinfunction "IN_6") (pintype "passive"))
      (node (ref "D15") (pin "4") (pinfunction "EN_4") (pintype "input"))
      (node (ref "D15") (pin "6") (pinfunction "IN_6") (pintype "passive"))
      (node (ref "D17") (pin "4") (pinfunction "EN_4") (pintype "input"))
      (node (ref "D17") (pin "6") (pinfunction "IN_6") (pintype "passive"))
      (node (ref "L20") (pin "2") (pinfunction "2_2") (pintype "passive"))
    )
    (net (code "36") (name "_12V_TPS") (class "Default")
      (node (ref "C105") (pin "2") (pinfunction "2_2") (pintype "passive"))
      (node (ref "C94") (pin "2") (pinfunction "2_2") (pintype "passive"))
      (node (ref "L19") (pin "1") (pinfunction "1_1") (pintype "passive"))
      (node (ref "R42") (pin "2") (pinfunction "2_2") (pintype "passive"))
      (node (ref "T4") (pin "2") (pinfunction "S_2") (pintype "passive"))
    )
    (net (code "37") (name "_TPS_DISDRV") (class "Default")
      (node (ref "C107") (pin "2") (pinfunction "2_2") (pintype "passive"))
      (node (ref "D12") (pin "9") (pinfunction "DISDRV_9") (pintype "passive"))
      (node (ref "R43") (pin "1") (pinfunction "1_1") (pintype "passive"))
      (node (ref "T4") (pin "1") (pinfunction "G_1") (pintype "passive"))
    )
    (net (code "38") (name "_TPS_FB") (class "Default")
      (node (ref "D12") (pin "5") (pinfunction "FB_5") (pintype "passive"))
      (node (ref "R42") (pin "1") (pinfunction "1_1") (pintype "passive"))
      (node (ref "R44") (pin "2") (pinfunction "2_2") (pintype "passive"))
    )
    (net (code "39") (name "_TPS_VOUT") (class "Default")
      (node (ref "C106") (pin "2") (pinfunction "2_2") (pintype "passive"))
      (node (ref "C107") (pin "1") (pinfunction "1_1") (pintype "passive"))
      (node (ref "D12") (pin "8") (pinfunction "VOUT_8") (pintype "passive"))
      (node (ref "R43") (pin "2") (pinfunction "2_2") (pintype "passive"))
      (node (ref "T4") (pin "3") (pinfunction "D_3") (pintype "passive"))
    )
  )
)
